# markey.net
KiCad netlist of a schematic drawn in EAGLE
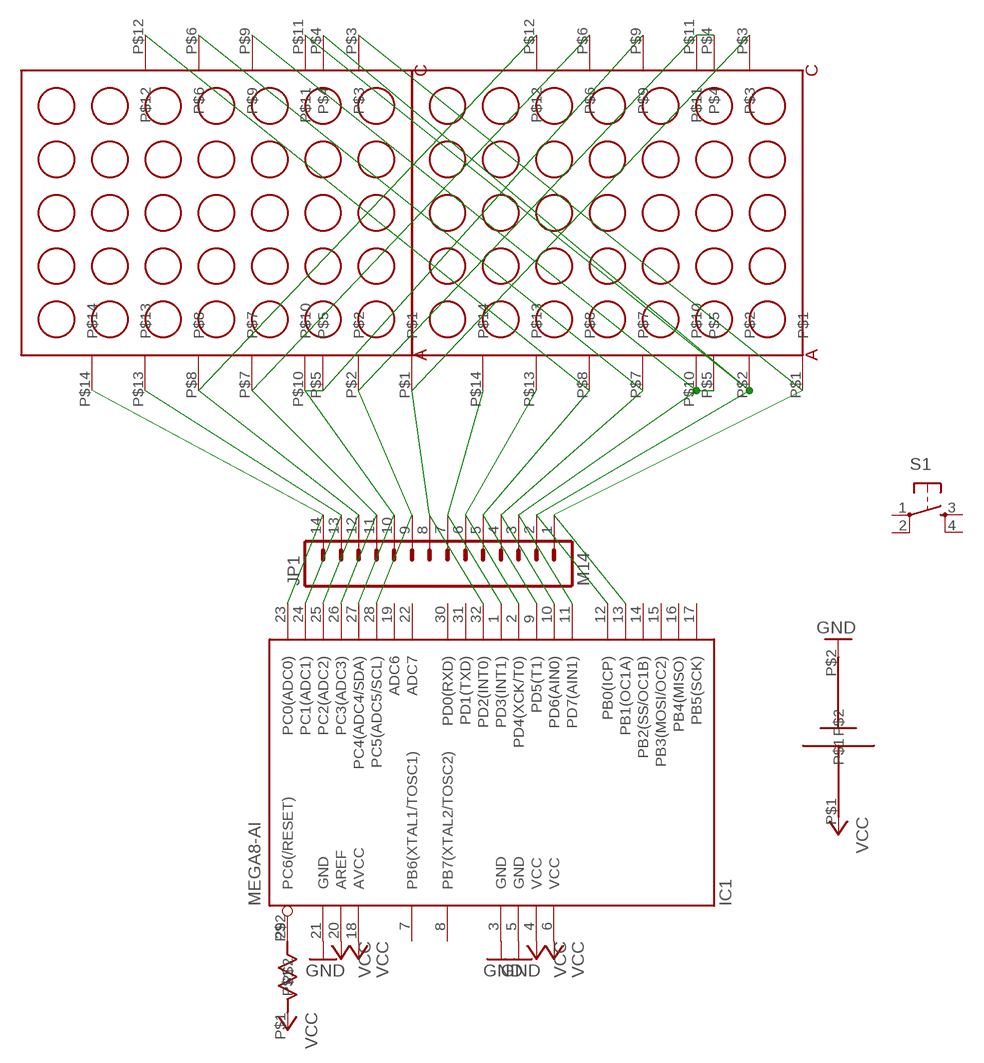
[diagram p0: schematic, sheet 1]

(export (version "E")
  (design (tool "Eeschema 10.0.6"))
  (components
    (comp (ref "IC1")
      (value "MEGA8-AI")
      (footprint "eagle-import:TQFP32-08")
      (fields (field (name "MPN") "ATMEGA8-16AU"))
      (libsource (lib "eagle-import") (part "MEGA8-AI"))
    )
    (comp (ref "JP1")
      (value "M14")
      (footprint "eagle-import:1X14")
      (libsource (lib "eagle-import") (part "M14"))
    )
    (comp (ref "S1")
      (value "TAC_SWITCHPTH")
      (footprint "eagle-import:TACTILE-PTH")
      (libsource (lib "eagle-import") (part "TAC_SWITCHPTH"))
    )
    (comp (ref "U$1")
      (value "5X7_SMALL_MX")
      (footprint "eagle-import:5X7")
      (libsource (lib "eagle-import") (part "5X7_SMALL_MX"))
    )
    (comp (ref "U$2")
      (value "5X7_SMALL_MX")
      (footprint "eagle-import:5X7")
      (libsource (lib "eagle-import") (part "5X7_SMALL_MX"))
    )
    (comp (ref "U$3")
      (value "R-7")
      (footprint "eagle-import:R-7")
      (libsource (lib "eagle-import") (part "R-7"))
    )
    (comp (ref "U$4")
      (value "CR2032")
      (footprint "eagle-import:CR2032_EBAY")
      (libsource (lib "eagle-import") (part "CR2032"))
    )
  )
  (nets
    (net (code "1") (name "GND") (class "Default")
      (node (ref "IC1") (pin "21") (pinfunction "GND_21") (pintype "power_in"))
      (node (ref "IC1") (pin "3") (pinfunction "GND_3") (pintype "power_in"))
      (node (ref "IC1") (pin "5") (pinfunction "GND_5") (pintype "power_in"))
      (node (ref "U$4") (pin "P$2") (pinfunction "P$2_P$2") (pintype "bidirectional"))
    )
    (net (code "2") (name "Net-(IC1-PB0(ICP))") (class "Default")
      (node (ref "IC1") (pin "12") (pinfunction "PB0(ICP)_12") (pintype "bidirectional"))
      (node (ref "JP1") (pin "2") (pinfunction "2_2") (pintype "passive"))
      (node (ref "U$1") (pin "P$2") (pinfunction "P$2_P$2") (pintype "bidirectional"))
      (node (ref "U$2") (pin "P$11") (pinfunction "P$11_P$11") (pintype "bidirectional"))
      (node (ref "U$2") (pin "P$4") (pinfunction "P$4_P$4") (pintype "bidirectional"))
    )
    (net (code "3") (name "Net-(IC1-PB1(OC1A))") (class "Default")
      (node (ref "IC1") (pin "13") (pinfunction "PB1(OC1A)_13") (pintype "bidirectional"))
      (node (ref "JP1") (pin "1") (pinfunction "1_1") (pintype "passive"))
      (node (ref "U$1") (pin "P$1") (pinfunction "P$1_P$1") (pintype "bidirectional"))
      (node (ref "U$2") (pin "P$3") (pinfunction "P$3_P$3") (pintype "bidirectional"))
    )
    (net (code "4") (name "Net-(IC1-PC0(ADC0))") (class "Default")
      (node (ref "IC1") (pin "23") (pinfunction "PC0(ADC0)_23") (pintype "bidirectional"))
      (node (ref "JP1") (pin "14") (pinfunction "14_14") (pintype "passive"))
      (node (ref "U$2") (pin "P$14") (pinfunction "P$14_P$14") (pintype "bidirectional"))
    )
    (net (code "5") (name "Net-(IC1-PC1(ADC1))") (class "Default")
      (node (ref "IC1") (pin "24") (pinfunction "PC1(ADC1)_24") (pintype "bidirectional"))
      (node (ref "JP1") (pin "13") (pinfunction "13_13") (pintype "passive"))
      (node (ref "U$2") (pin "P$13") (pinfunction "P$13_P$13") (pintype "bidirectional"))
    )
    (net (code "6") (name "Net-(IC1-PC2(ADC2))") (class "Default")
      (node (ref "IC1") (pin "25") (pinfunction "PC2(ADC2)_25") (pintype "bidirectional"))
      (node (ref "JP1") (pin "12") (pinfunction "12_12") (pintype "passive"))
      (node (ref "U$1") (pin "P$12") (pinfunction "P$12_P$12") (pintype "bidirectional"))
      (node (ref "U$2") (pin "P$8") (pinfunction "P$8_P$8") (pintype "bidirectional"))
    )
    (net (code "7") (name "Net-(IC1-PC3(ADC3))") (class "Default")
      (node (ref "IC1") (pin "26") (pinfunction "PC3(ADC3)_26") (pintype "bidirectional"))
      (node (ref "JP1") (pin "11") (pinfunction "11_11") (pintype "passive"))
      (node (ref "U$1") (pin "P$6") (pinfunction "P$6_P$6") (pintype "bidirectional"))
      (node (ref "U$2") (pin "P$7") (pinfunction "P$7_P$7") (pintype "bidirectional"))
    )
    (net (code "8") (name "Net-(IC1-PC4(ADC4{slash}SDA))") (class "Default")
      (node (ref "IC1") (pin "27") (pinfunction "PC4(ADC4/SDA)_27") (pintype "bidirectional"))
      (node (ref "JP1") (pin "10") (pinfunction "10_10") (pintype "passive"))
      (node (ref "U$1") (pin "P$9") (pinfunction "P$9_P$9") (pintype "bidirectional"))
      (node (ref "U$2") (pin "P$10") (pinfunction "P$10_P$10") (pintype "bidirectional"))
      (node (ref "U$2") (pin "P$5") (pinfunction "P$5_P$5") (pintype "bidirectional"))
    )
    (net (code "9") (name "Net-(IC1-PC5(ADC5{slash}SCL))") (class "Default")
      (node (ref "IC1") (pin "28") (pinfunction "PC5(ADC5/SCL)_28") (pintype "bidirectional"))
      (node (ref "JP1") (pin "9") (pinfunction "9_9") (pintype "passive"))
      (node (ref "U$1") (pin "P$11") (pinfunction "P$11_P$11") (pintype "bidirectional"))
      (node (ref "U$1") (pin "P$4") (pinfunction "P$4_P$4") (pintype "bidirectional"))
      (node (ref "U$2") (pin "P$2") (pinfunction "P$2_P$2") (pintype "bidirectional"))
    )
    (net (code "10") (name "Net-(IC1-PC6({slash}RESET))") (class "Default")
      (node (ref "IC1") (pin "29") (pinfunction "PC6(/RESET)_29") (pintype "bidirectional"))
      (node (ref "U$3") (pin "P$2") (pinfunction "P$2_P$2") (pintype "bidirectional"))
    )
    (net (code "11") (name "Net-(IC1-PD2(INT0))") (class "Default")
      (node (ref "IC1") (pin "32") (pinfunction "PD2(INT0)_32") (pintype "bidirectional"))
      (node (ref "JP1") (pin "8") (pinfunction "8_8") (pintype "passive"))
      (node (ref "U$1") (pin "P$3") (pinfunction "P$3_P$3") (pintype "bidirectional"))
      (node (ref "U$2") (pin "P$1") (pinfunction "P$1_P$1") (pintype "bidirectional"))
    )
    (net (code "12") (name "Net-(IC1-PD3(INT1))") (class "Default")
      (node (ref "IC1") (pin "1") (pinfunction "PD3(INT1)_1") (pintype "bidirectional"))
      (node (ref "JP1") (pin "7") (pinfunction "7_7") (pintype "passive"))
      (node (ref "U$1") (pin "P$14") (pinfunction "P$14_P$14") (pintype "bidirectional"))
    )
    (net (code "13") (name "Net-(IC1-PD4(XCK{slash}T0))") (class "Default")
      (node (ref "IC1") (pin "2") (pinfunction "PD4(XCK/T0)_2") (pintype "bidirectional"))
      (node (ref "JP1") (pin "6") (pinfunction "6_6") (pintype "passive"))
      (node (ref "U$1") (pin "P$13") (pinfunction "P$13_P$13") (pintype "bidirectional"))
    )
    (net (code "14") (name "Net-(IC1-PD5(T1))") (class "Default")
      (node (ref "IC1") (pin "9") (pinfunction "PD5(T1)_9") (pintype "bidirectional"))
      (node (ref "JP1") (pin "5") (pinfunction "5_5") (pintype "passive"))
      (node (ref "U$1") (pin "P$8") (pinfunction "P$8_P$8") (pintype "bidirectional"))
      (node (ref "U$2") (pin "P$12") (pinfunction "P$12_P$12") (pintype "bidirectional"))
    )
    (net (code "15") (name "Net-(IC1-PD6(AIN0))") (class "Default")
      (node (ref "IC1") (pin "10") (pinfunction "PD6(AIN0)_10") (pintype "bidirectional"))
      (node (ref "JP1") (pin "4") (pinfunction "4_4") (pintype "passive"))
      (node (ref "U$1") (pin "P$7") (pinfunction "P$7_P$7") (pintype "bidirectional"))
      (node (ref "U$2") (pin "P$6") (pinfunction "P$6_P$6") (pintype "bidirectional"))
    )
    (net (code "16") (name "Net-(IC1-PD7(AIN1))") (class "Default")
      (node (ref "IC1") (pin "11") (pinfunction "PD7(AIN1)_11") (pintype "bidirectional"))
      (node (ref "JP1") (pin "3") (pinfunction "3_3") (pintype "passive"))
      (node (ref "U$1") (pin "P$10") (pinfunction "P$10_P$10") (pintype "bidirectional"))
      (node (ref "U$1") (pin "P$5") (pinfunction "P$5_P$5") (pintype "bidirectional"))
      (node (ref "U$2") (pin "P$9") (pinfunction "P$9_P$9") (pintype "bidirectional"))
    )
    (net (code "17") (name "VCC") (class "Default")
      (node (ref "IC1") (pin "18") (pinfunction "AVCC_18") (pintype "power_in"))
      (node (ref "IC1") (pin "20") (pinfunction "AREF_20") (pintype "passive"))
      (node (ref "IC1") (pin "4") (pinfunction "VCC_4") (pintype "power_in"))
      (node (ref "IC1") (pin "6") (pinfunction "VCC_6") (pintype "power_in"))
      (node (ref "U$3") (pin "P$1") (pinfunction "P$1_P$1") (pintype "bidirectional"))
      (node (ref "U$4") (pin "P$1") (pinfunction "P$1_P$1") (pintype "bidirectional"))
    )
    (net (code "18") (name "unconnected-(IC1-ADC6-Pad19)") (class "Default")
      (node (ref "IC1") (pin "19") (pinfunction "ADC6_19") (pintype "bidirectional"))
    )
    (net (code "19") (name "unconnected-(IC1-ADC7-Pad22)") (class "Default")
      (node (ref "IC1") (pin "22") (pinfunction "ADC7_22") (pintype "bidirectional"))
    )
    (net (code "20") (name "unconnected-(IC1-PB2(SS{slash}OC1B)-Pad14)") (class "Default")
      (node (ref "IC1") (pin "14") (pinfunction "PB2(SS/OC1B)_14") (pintype "bidirectional"))
    )
    (net (code "21") (name "unconnected-(IC1-PB3(MOSI{slash}OC2)-Pad15)") (class "Default")
      (node (ref "IC1") (pin "15") (pinfunction "PB3(MOSI/OC2)_15") (pintype "bidirectional"))
    )
    (net (code "22") (name "unconnected-(IC1-PB4(MISO)-Pad16)") (class "Default")
      (node (ref "IC1") (pin "16") (pinfunction "PB4(MISO)_16") (pintype "bidirectional"))
    )
    (net (code "23") (name "unconnected-(IC1-PB5(SCK)-Pad17)") (class "Default")
      (node (ref "IC1") (pin "17") (pinfunction "PB5(SCK)_17") (pintype "bidirectional"))
    )
    (net (code "24") (name "unconnected-(IC1-PB6(XTAL1{slash}TOSC1)-Pad7)") (class "Default")
      (node (ref "IC1") (pin "7") (pinfunction "PB6(XTAL1/TOSC1)_7") (pintype "bidirectional"))
    )
    (net (code "25") (name "unconnected-(IC1-PB7(XTAL2{slash}TOSC2)-Pad8)") (class "Default")
      (node (ref "IC1") (pin "8") (pinfunction "PB7(XTAL2/TOSC2)_8") (pintype "bidirectional"))
    )
    (net (code "26") (name "unconnected-(IC1-PD0(RXD)-Pad30)") (class "Default")
      (node (ref "IC1") (pin "30") (pinfunction "PD0(RXD)_30") (pintype "bidirectional"))
    )
    (net (code "27") (name "unconnected-(IC1-PD1(TXD)-Pad31)") (class "Default")
      (node (ref "IC1") (pin "31") (pinfunction "PD1(TXD)_31") (pintype "bidirectional"))
    )
    (net (code "28") (name "unconnected-(S1-Pad1)") (class "Default")
      (node (ref "S1") (pin "1") (pinfunction "1_1") (pintype "passive"))
    )
    (net (code "29") (name "unconnected-(S1-Pad2)") (class "Default")
      (node (ref "S1") (pin "2") (pinfunction "2_2") (pintype "passive"))
    )
    (net (code "30") (name "unconnected-(S1-Pad3)") (class "Default")
      (node (ref "S1") (pin "3") (pinfunction "3_3") (pintype "passive"))
    )
    (net (code "31") (name "unconnected-(S1-Pad4)") (class "Default")
      (node (ref "S1") (pin "4") (pinfunction "4_4") (pintype "passive"))
    )
  )
)
